# ADC_IN.net
KiCad netlist of a schematic drawn in Altium Designer
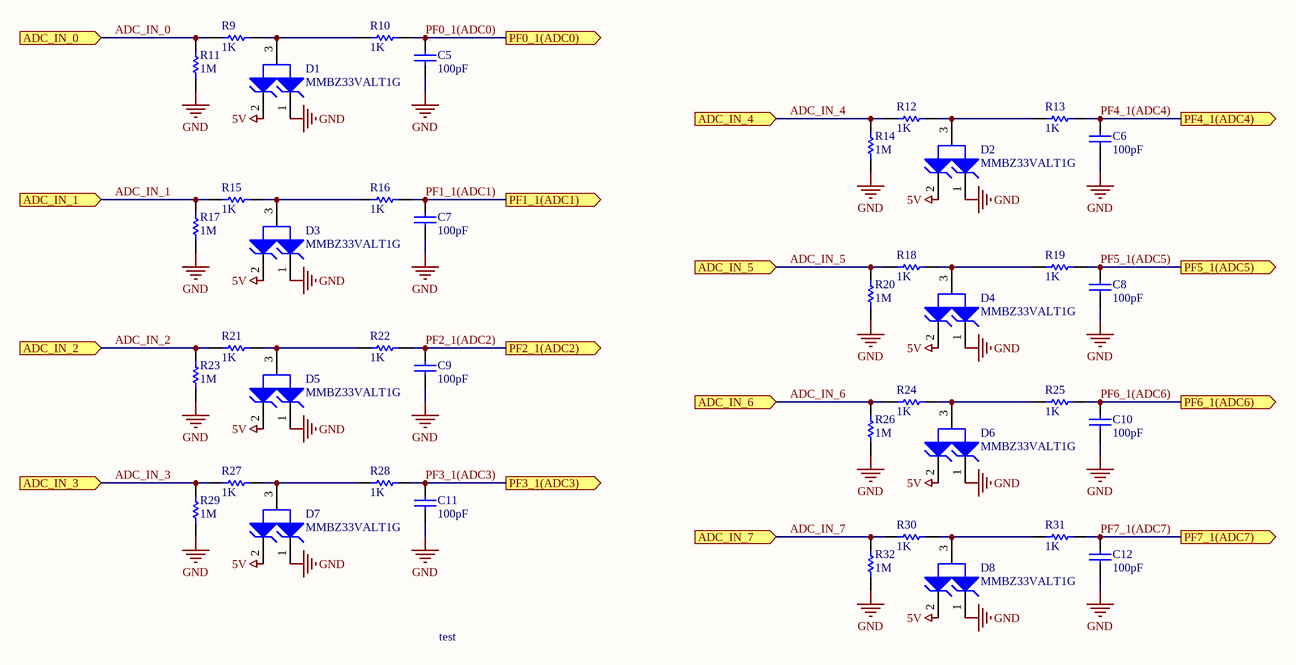
[diagram p0: ADC_IN.SchDoc]

(export (version "E")
  (design (tool "Eeschema 10.0.6"))
  (components
    (comp (ref "C5")
      (value "100pF")
      (footprint "CAPC2013X140X50NL20T25")
      (fields
        (field (name "MANUFACTURER") "AVX Interconnect / Elco")
        (field (name "PART NUMBER") "08051A102JAT2A")
      )
      (libsource (lib "project") (part "CAP"))
    )
    (comp (ref "C6")
      (value "100pF")
      (footprint "CAPC2013X140X50NL20T25")
      (fields
        (field (name "MANUFACTURER") "AVX Interconnect / Elco")
        (field (name "PART NUMBER") "08051A102JAT2A")
      )
      (libsource (lib "project") (part "CAP"))
    )
    (comp (ref "C7")
      (value "100pF")
      (footprint "CAPC2013X140X50NL20T25")
      (fields
        (field (name "MANUFACTURER") "AVX Interconnect / Elco")
        (field (name "PART NUMBER") "08051A102JAT2A")
      )
      (libsource (lib "project") (part "CAP"))
    )
    (comp (ref "C8")
      (value "100pF")
      (footprint "CAPC2013X140X50NL20T25")
      (fields
        (field (name "MANUFACTURER") "AVX Interconnect / Elco")
        (field (name "PART NUMBER") "08051A102JAT2A")
      )
      (libsource (lib "project") (part "CAP"))
    )
    (comp (ref "C9")
      (value "100pF")
      (footprint "CAPC2013X140X50NL20T25")
      (fields
        (field (name "MANUFACTURER") "AVX Interconnect / Elco")
        (field (name "PART NUMBER") "08051A102JAT2A")
      )
      (libsource (lib "project") (part "CAP"))
    )
    (comp (ref "C10")
      (value "100pF")
      (footprint "CAPC2013X140X50NL20T25")
      (fields
        (field (name "MANUFACTURER") "AVX Interconnect / Elco")
        (field (name "PART NUMBER") "08051A102JAT2A")
      )
      (libsource (lib "project") (part "CAP"))
    )
    (comp (ref "C11")
      (value "100pF")
      (footprint "CAPC2013X140X50NL20T25")
      (fields
        (field (name "MANUFACTURER") "AVX Interconnect / Elco")
        (field (name "PART NUMBER") "08051A102JAT2A")
      )
      (libsource (lib "project") (part "CAP"))
    )
    (comp (ref "C12")
      (value "100pF")
      (footprint "CAPC2013X140X50NL20T25")
      (fields
        (field (name "MANUFACTURER") "AVX Interconnect / Elco")
        (field (name "PART NUMBER") "08051A102JAT2A")
      )
      (libsource (lib "project") (part "CAP"))
    )
    (comp (ref "D1")
      (value "MMBZ33VALT1G")
      (footprint "ONSC-SOT-23-3-318-08_V")
      (fields (field (name "MANUFACTURER") "On Semiconductor"))
      (libsource (lib "project") (part "ONSC-K1K2A3-3"))
    )
    (comp (ref "D2")
      (value "MMBZ33VALT1G")
      (footprint "ONSC-SOT-23-3-318-08_V")
      (fields (field (name "MANUFACTURER") "On Semiconductor"))
      (libsource (lib "project") (part "ONSC-K1K2A3-3"))
    )
    (comp (ref "D3")
      (value "MMBZ33VALT1G")
      (footprint "ONSC-SOT-23-3-318-08_V")
      (fields (field (name "MANUFACTURER") "On Semiconductor"))
      (libsource (lib "project") (part "ONSC-K1K2A3-3"))
    )
    (comp (ref "D4")
      (value "MMBZ33VALT1G")
      (footprint "ONSC-SOT-23-3-318-08_V")
      (fields (field (name "MANUFACTURER") "On Semiconductor"))
      (libsource (lib "project") (part "ONSC-K1K2A3-3"))
    )
    (comp (ref "D5")
      (value "MMBZ33VALT1G")
      (footprint "ONSC-SOT-23-3-318-08_V")
      (fields (field (name "MANUFACTURER") "On Semiconductor"))
      (libsource (lib "project") (part "ONSC-K1K2A3-3"))
    )
    (comp (ref "D6")
      (value "MMBZ33VALT1G")
      (footprint "ONSC-SOT-23-3-318-08_V")
      (fields (field (name "MANUFACTURER") "On Semiconductor"))
      (libsource (lib "project") (part "ONSC-K1K2A3-3"))
    )
    (comp (ref "D7")
      (value "MMBZ33VALT1G")
      (footprint "ONSC-SOT-23-3-318-08_V")
      (fields (field (name "MANUFACTURER") "On Semiconductor"))
      (libsource (lib "project") (part "ONSC-K1K2A3-3"))
    )
    (comp (ref "D8")
      (value "MMBZ33VALT1G")
      (footprint "ONSC-SOT-23-3-318-08_V")
      (fields (field (name "MANUFACTURER") "On Semiconductor"))
      (libsource (lib "project") (part "ONSC-K1K2A3-3"))
    )
    (comp (ref "R9")
      (value "1K")
      (footprint "RESC2113X50X35ML15T15")
      (description "Chip Resistor, 4.7 KOhm, +/- 1%, 0.125 W, -55 to 155 degC, 0805 (2012 Metric), RoHS, Tape and Reel")
      (fields (field (name "TOLERANCE") "1%") (field (name "MANUFACTURER") "Vishay Semiconductor"))
      (libsource (lib "project") (part "RES-2"))
    )
    (comp (ref "R10")
      (value "1K")
      (footprint "RESC2113X50X35ML15T15")
      (description "Chip Resistor, 4.7 KOhm, +/- 1%, 0.125 W, -55 to 155 degC, 0805 (2012 Metric), RoHS, Tape and Reel")
      (fields (field (name "TOLERANCE") "1%") (field (name "MANUFACTURER") "Vishay Semiconductor"))
      (libsource (lib "project") (part "RES-2"))
    )
    (comp (ref "R11")
      (value "1M")
      (footprint "RESC2113X50X35ML15T15")
      (description "Chip Resistor, 4.7 KOhm, +/- 1%, 0.125 W, -55 to 155 degC, 0805 (2012 Metric), RoHS, Tape and Reel")
      (fields (field (name "TOLERANCE") "1%") (field (name "MANUFACTURER") "Vishay Semiconductor"))
      (libsource (lib "project") (part "RES-2"))
    )
    (comp (ref "R12")
      (value "1K")
      (footprint "RESC2113X50X35ML15T15")
      (description "Chip Resistor, 4.7 KOhm, +/- 1%, 0.125 W, -55 to 155 degC, 0805 (2012 Metric), RoHS, Tape and Reel")
      (fields (field (name "TOLERANCE") "1%") (field (name "MANUFACTURER") "Vishay Semiconductor"))
      (libsource (lib "project") (part "RES-2"))
    )
    (comp (ref "R13")
      (value "1K")
      (footprint "RESC2113X50X35ML15T15")
      (description "Chip Resistor, 4.7 KOhm, +/- 1%, 0.125 W, -55 to 155 degC, 0805 (2012 Metric), RoHS, Tape and Reel")
      (fields (field (name "TOLERANCE") "1%") (field (name "MANUFACTURER") "Vishay Semiconductor"))
      (libsource (lib "project") (part "RES-2"))
    )
    (comp (ref "R14")
      (value "1M")
      (footprint "RESC2113X50X35ML15T15")
      (description "Chip Resistor, 4.7 KOhm, +/- 1%, 0.125 W, -55 to 155 degC, 0805 (2012 Metric), RoHS, Tape and Reel")
      (fields (field (name "TOLERANCE") "1%") (field (name "MANUFACTURER") "Vishay Semiconductor"))
      (libsource (lib "project") (part "RES-2"))
    )
    (comp (ref "R15")
      (value "1K")
      (footprint "RESC2113X50X35ML15T15")
      (description "Chip Resistor, 4.7 KOhm, +/- 1%, 0.125 W, -55 to 155 degC, 0805 (2012 Metric), RoHS, Tape and Reel")
      (fields (field (name "TOLERANCE") "1%") (field (name "MANUFACTURER") "Vishay Semiconductor"))
      (libsource (lib "project") (part "RES-2"))
    )
    (comp (ref "R16")
      (value "1K")
      (footprint "RESC2113X50X35ML15T15")
      (description "Chip Resistor, 4.7 KOhm, +/- 1%, 0.125 W, -55 to 155 degC, 0805 (2012 Metric), RoHS, Tape and Reel")
      (fields (field (name "TOLERANCE") "1%") (field (name "MANUFACTURER") "Vishay Semiconductor"))
      (libsource (lib "project") (part "RES-2"))
    )
    (comp (ref "R17")
      (value "1M")
      (footprint "RESC2113X50X35ML15T15")
      (description "Chip Resistor, 4.7 KOhm, +/- 1%, 0.125 W, -55 to 155 degC, 0805 (2012 Metric), RoHS, Tape and Reel")
      (fields (field (name "TOLERANCE") "1%") (field (name "MANUFACTURER") "Vishay Semiconductor"))
      (libsource (lib "project") (part "RES-2"))
    )
    (comp (ref "R18")
      (value "1K")
      (footprint "RESC2113X50X35ML15T15")
      (description "Chip Resistor, 4.7 KOhm, +/- 1%, 0.125 W, -55 to 155 degC, 0805 (2012 Metric), RoHS, Tape and Reel")
      (fields (field (name "TOLERANCE") "1%") (field (name "MANUFACTURER") "Vishay Semiconductor"))
      (libsource (lib "project") (part "RES-2"))
    )
    (comp (ref "R19")
      (value "1K")
      (footprint "RESC2113X50X35ML15T15")
      (description "Chip Resistor, 4.7 KOhm, +/- 1%, 0.125 W, -55 to 155 degC, 0805 (2012 Metric), RoHS, Tape and Reel")
      (fields (field (name "TOLERANCE") "1%") (field (name "MANUFACTURER") "Vishay Semiconductor"))
      (libsource (lib "project") (part "RES-2"))
    )
    (comp (ref "R20")
      (value "1M")
      (footprint "RESC2113X50X35ML15T15")
      (description "Chip Resistor, 4.7 KOhm, +/- 1%, 0.125 W, -55 to 155 degC, 0805 (2012 Metric), RoHS, Tape and Reel")
      (fields (field (name "TOLERANCE") "1%") (field (name "MANUFACTURER") "Vishay Semiconductor"))
      (libsource (lib "project") (part "RES-2"))
    )
    (comp (ref "R21")
      (value "1K")
      (footprint "RESC2113X50X35ML15T15")
      (description "Chip Resistor, 4.7 KOhm, +/- 1%, 0.125 W, -55 to 155 degC, 0805 (2012 Metric), RoHS, Tape and Reel")
      (fields (field (name "TOLERANCE") "1%") (field (name "MANUFACTURER") "Vishay Semiconductor"))
      (libsource (lib "project") (part "RES-2"))
    )
    (comp (ref "R22")
      (value "1K")
      (footprint "RESC2113X50X35ML15T15")
      (description "Chip Resistor, 4.7 KOhm, +/- 1%, 0.125 W, -55 to 155 degC, 0805 (2012 Metric), RoHS, Tape and Reel")
      (fields (field (name "TOLERANCE") "1%") (field (name "MANUFACTURER") "Vishay Semiconductor"))
      (libsource (lib "project") (part "RES-2"))
    )
    (comp (ref "R23")
      (value "1M")
      (footprint "RESC2113X50X35ML15T15")
      (description "Chip Resistor, 4.7 KOhm, +/- 1%, 0.125 W, -55 to 155 degC, 0805 (2012 Metric), RoHS, Tape and Reel")
      (fields (field (name "TOLERANCE") "1%") (field (name "MANUFACTURER") "Vishay Semiconductor"))
      (libsource (lib "project") (part "RES-2"))
    )
    (comp (ref "R24")
      (value "1K")
      (footprint "RESC2113X50X35ML15T15")
      (description "Chip Resistor, 4.7 KOhm, +/- 1%, 0.125 W, -55 to 155 degC, 0805 (2012 Metric), RoHS, Tape and Reel")
      (fields (field (name "TOLERANCE") "1%") (field (name "MANUFACTURER") "Vishay Semiconductor"))
      (libsource (lib "project") (part "RES-2"))
    )
    (comp (ref "R25")
      (value "1K")
      (footprint "RESC2113X50X35ML15T15")
      (description "Chip Resistor, 4.7 KOhm, +/- 1%, 0.125 W, -55 to 155 degC, 0805 (2012 Metric), RoHS, Tape and Reel")
      (fields (field (name "TOLERANCE") "1%") (field (name "MANUFACTURER") "Vishay Semiconductor"))
      (libsource (lib "project") (part "RES-2"))
    )
    (comp (ref "R26")
      (value "1M")
      (footprint "RESC2113X50X35ML15T15")
      (description "Chip Resistor, 4.7 KOhm, +/- 1%, 0.125 W, -55 to 155 degC, 0805 (2012 Metric), RoHS, Tape and Reel")
      (fields (field (name "TOLERANCE") "1%") (field (name "MANUFACTURER") "Vishay Semiconductor"))
      (libsource (lib "project") (part "RES-2"))
    )
    (comp (ref "R27")
      (value "1K")
      (footprint "RESC2113X50X35ML15T15")
      (description "Chip Resistor, 4.7 KOhm, +/- 1%, 0.125 W, -55 to 155 degC, 0805 (2012 Metric), RoHS, Tape and Reel")
      (fields (field (name "TOLERANCE") "1%") (field (name "MANUFACTURER") "Vishay Semiconductor"))
      (libsource (lib "project") (part "RES-2"))
    )
    (comp (ref "R28")
      (value "1K")
      (footprint "RESC2113X50X35ML15T15")
      (description "Chip Resistor, 4.7 KOhm, +/- 1%, 0.125 W, -55 to 155 degC, 0805 (2012 Metric), RoHS, Tape and Reel")
      (fields (field (name "TOLERANCE") "1%") (field (name "MANUFACTURER") "Vishay Semiconductor"))
      (libsource (lib "project") (part "RES-2"))
    )
    (comp (ref "R29")
      (value "1M")
      (footprint "RESC2113X50X35ML15T15")
      (description "Chip Resistor, 4.7 KOhm, +/- 1%, 0.125 W, -55 to 155 degC, 0805 (2012 Metric), RoHS, Tape and Reel")
      (fields (field (name "TOLERANCE") "1%") (field (name "MANUFACTURER") "Vishay Semiconductor"))
      (libsource (lib "project") (part "RES-2"))
    )
    (comp (ref "R30")
      (value "1K")
      (footprint "RESC2113X50X35ML15T15")
      (description "Chip Resistor, 4.7 KOhm, +/- 1%, 0.125 W, -55 to 155 degC, 0805 (2012 Metric), RoHS, Tape and Reel")
      (fields (field (name "TOLERANCE") "1%") (field (name "MANUFACTURER") "Vishay Semiconductor"))
      (libsource (lib "project") (part "RES-2"))
    )
    (comp (ref "R31")
      (value "1K")
      (footprint "RESC2113X50X35ML15T15")
      (description "Chip Resistor, 4.7 KOhm, +/- 1%, 0.125 W, -55 to 155 degC, 0805 (2012 Metric), RoHS, Tape and Reel")
      (fields (field (name "TOLERANCE") "1%") (field (name "MANUFACTURER") "Vishay Semiconductor"))
      (libsource (lib "project") (part "RES-2"))
    )
    (comp (ref "R32")
      (value "1M")
      (footprint "RESC2113X50X35ML15T15")
      (description "Chip Resistor, 4.7 KOhm, +/- 1%, 0.125 W, -55 to 155 degC, 0805 (2012 Metric), RoHS, Tape and Reel")
      (fields (field (name "TOLERANCE") "1%") (field (name "MANUFACTURER") "Vishay Semiconductor"))
      (libsource (lib "project") (part "RES-2"))
    )
  )
  (nets
    (net (code "1") (name "/ADC_IN_0") (class "Default")
      (node (ref "R11") (pin "1") (pinfunction "1_1") (pintype "passive"))
      (node (ref "R9") (pin "2") (pinfunction "2_2") (pintype "passive"))
    )
    (net (code "2") (name "/ADC_IN_1") (class "Default")
      (node (ref "R15") (pin "2") (pinfunction "2_2") (pintype "passive"))
      (node (ref "R17") (pin "1") (pinfunction "1_1") (pintype "passive"))
    )
    (net (code "3") (name "/ADC_IN_2") (class "Default")
      (node (ref "R21") (pin "2") (pinfunction "2_2") (pintype "passive"))
      (node (ref "R23") (pin "1") (pinfunction "1_1") (pintype "passive"))
    )
    (net (code "4") (name "/ADC_IN_3") (class "Default")
      (node (ref "R27") (pin "2") (pinfunction "2_2") (pintype "passive"))
      (node (ref "R29") (pin "1") (pinfunction "1_1") (pintype "passive"))
    )
    (net (code "5") (name "/ADC_IN_4") (class "Default")
      (node (ref "R12") (pin "2") (pinfunction "2_2") (pintype "passive"))
      (node (ref "R14") (pin "1") (pinfunction "1_1") (pintype "passive"))
    )
    (net (code "6") (name "/ADC_IN_5") (class "Default")
      (node (ref "R18") (pin "2") (pinfunction "2_2") (pintype "passive"))
      (node (ref "R20") (pin "1") (pinfunction "1_1") (pintype "passive"))
    )
    (net (code "7") (name "/ADC_IN_6") (class "Default")
      (node (ref "R24") (pin "2") (pinfunction "2_2") (pintype "passive"))
      (node (ref "R26") (pin "1") (pinfunction "1_1") (pintype "passive"))
    )
    (net (code "8") (name "/ADC_IN_7") (class "Default")
      (node (ref "R30") (pin "2") (pinfunction "2_2") (pintype "passive"))
      (node (ref "R32") (pin "1") (pinfunction "1_1") (pintype "passive"))
    )
    (net (code "9") (name "/PF0_1(ADC0)") (class "Default")
      (node (ref "C5") (pin "1") (pinfunction "1_1") (pintype "passive"))
      (node (ref "R10") (pin "1") (pinfunction "1_1") (pintype "passive"))
    )
    (net (code "10") (name "/PF1_1(ADC1)") (class "Default")
      (node (ref "C7") (pin "1") (pinfunction "1_1") (pintype "passive"))
      (node (ref "R16") (pin "1") (pinfunction "1_1") (pintype "passive"))
    )
    (net (code "11") (name "/PF2_1(ADC2)") (class "Default")
      (node (ref "C9") (pin "1") (pinfunction "1_1") (pintype "passive"))
      (node (ref "R22") (pin "1") (pinfunction "1_1") (pintype "passive"))
    )
    (net (code "12") (name "/PF3_1(ADC3)") (class "Default")
      (node (ref "C11") (pin "1") (pinfunction "1_1") (pintype "passive"))
      (node (ref "R28") (pin "1") (pinfunction "1_1") (pintype "passive"))
    )
    (net (code "13") (name "/PF4_1(ADC4)") (class "Default")
      (node (ref "C6") (pin "1") (pinfunction "1_1") (pintype "passive"))
      (node (ref "R13") (pin "1") (pinfunction "1_1") (pintype "passive"))
    )
    (net (code "14") (name "/PF5_1(ADC5)") (class "Default")
      (node (ref "C8") (pin "1") (pinfunction "1_1") (pintype "passive"))
      (node (ref "R19") (pin "1") (pinfunction "1_1") (pintype "passive"))
    )
    (net (code "15") (name "/PF6_1(ADC6)") (class "Default")
      (node (ref "C10") (pin "1") (pinfunction "1_1") (pintype "passive"))
      (node (ref "R25") (pin "1") (pinfunction "1_1") (pintype "passive"))
    )
    (net (code "16") (name "/PF7_1(ADC7)") (class "Default")
      (node (ref "C12") (pin "1") (pinfunction "1_1") (pintype "passive"))
      (node (ref "R31") (pin "1") (pinfunction "1_1") (pintype "passive"))
    )
    (net (code "17") (name "5V") (class "Default")
      (node (ref "D1") (pin "2") (pinfunction "K2_2") (pintype "passive"))
      (node (ref "D2") (pin "2") (pinfunction "K2_2") (pintype "passive"))
      (node (ref "D3") (pin "2") (pinfunction "K2_2") (pintype "passive"))
      (node (ref "D4") (pin "2") (pinfunction "K2_2") (pintype "passive"))
      (node (ref "D5") (pin "2") (pinfunction "K2_2") (pintype "passive"))
      (node (ref "D6") (pin "2") (pinfunction "K2_2") (pintype "passive"))
      (node (ref "D7") (pin "2") (pinfunction "K2_2") (pintype "passive"))
      (node (ref "D8") (pin "2") (pinfunction "K2_2") (pintype "passive"))
    )
    (net (code "18") (name "GND") (class "Default")
      (node (ref "C10") (pin "2") (pinfunction "2_2") (pintype "passive"))
      (node (ref "C11") (pin "2") (pinfunction "2_2") (pintype "passive"))
      (node (ref "C12") (pin "2") (pinfunction "2_2") (pintype "passive"))
      (node (ref "C5") (pin "2") (pinfunction "2_2") (pintype "passive"))
      (node (ref "C6") (pin "2") (pinfunction "2_2") (pintype "passive"))
      (node (ref "C7") (pin "2") (pinfunction "2_2") (pintype "passive"))
      (node (ref "C8") (pin "2") (pinfunction "2_2") (pintype "passive"))
      (node (ref "C9") (pin "2") (pinfunction "2_2") (pintype "passive"))
      (node (ref "D1") (pin "1") (pinfunction "K1_1") (pintype "passive"))
      (node (ref "D2") (pin "1") (pinfunction "K1_1") (pintype "passive"))
      (node (ref "D3") (pin "1") (pinfunction "K1_1") (pintype "passive"))
      (node (ref "D4") (pin "1") (pinfunction "K1_1") (pintype "passive"))
      (node (ref "D5") (pin "1") (pinfunction "K1_1") (pintype "passive"))
      (node (ref "D6") (pin "1") (pinfunction "K1_1") (pintype "passive"))
      (node (ref "D7") (pin "1") (pinfunction "K1_1") (pintype "passive"))
      (node (ref "D8") (pin "1") (pinfunction "K1_1") (pintype "passive"))
      (node (ref "R11") (pin "2") (pinfunction "2_2") (pintype "passive"))
      (node (ref "R14") (pin "2") (pinfunction "2_2") (pintype "passive"))
      (node (ref "R17") (pin "2") (pinfunction "2_2") (pintype "passive"))
      (node (ref "R20") (pin "2") (pinfunction "2_2") (pintype "passive"))
      (node (ref "R23") (pin "2") (pinfunction "2_2") (pintype "passive"))
      (node (ref "R26") (pin "2") (pinfunction "2_2") (pintype "passive"))
      (node (ref "R29") (pin "2") (pinfunction "2_2") (pintype "passive"))
      (node (ref "R32") (pin "2") (pinfunction "2_2") (pintype "passive"))
    )
    (net (code "19") (name "Net-(D1-A)") (class "Default")
      (node (ref "D1") (pin "3") (pinfunction "A_3") (pintype "passive"))
      (node (ref "R10") (pin "2") (pinfunction "2_2") (pintype "passive"))
      (node (ref "R9") (pin "1") (pinfunction "1_1") (pintype "passive"))
    )
    (net (code "20") (name "Net-(D2-A)") (class "Default")
      (node (ref "D2") (pin "3") (pinfunction "A_3") (pintype "passive"))
      (node (ref "R12") (pin "1") (pinfunction "1_1") (pintype "passive"))
      (node (ref "R13") (pin "2") (pinfunction "2_2") (pintype "passive"))
    )
    (net (code "21") (name "Net-(D3-A)") (class "Default")
      (node (ref "D3") (pin "3") (pinfunction "A_3") (pintype "passive"))
      (node (ref "R15") (pin "1") (pinfunction "1_1") (pintype "passive"))
      (node (ref "R16") (pin "2") (pinfunction "2_2") (pintype "passive"))
    )
    (net (code "22") (name "Net-(D4-A)") (class "Default")
      (node (ref "D4") (pin "3") (pinfunction "A_3") (pintype "passive"))
      (node (ref "R18") (pin "1") (pinfunction "1_1") (pintype "passive"))
      (node (ref "R19") (pin "2") (pinfunction "2_2") (pintype "passive"))
    )
    (net (code "23") (name "Net-(D5-A)") (class "Default")
      (node (ref "D5") (pin "3") (pinfunction "A_3") (pintype "passive"))
      (node (ref "R21") (pin "1") (pinfunction "1_1") (pintype "passive"))
      (node (ref "R22") (pin "2") (pinfunction "2_2") (pintype "passive"))
    )
    (net (code "24") (name "Net-(D6-A)") (class "Default")
      (node (ref "D6") (pin "3") (pinfunction "A_3") (pintype "passive"))
      (node (ref "R24") (pin "1") (pinfunction "1_1") (pintype "passive"))
      (node (ref "R25") (pin "2") (pinfunction "2_2") (pintype "passive"))
    )
    (net (code "25") (name "Net-(D7-A)") (class "Default")
      (node (ref "D7") (pin "3") (pinfunction "A_3") (pintype "passive"))
      (node (ref "R27") (pin "1") (pinfunction "1_1") (pintype "passive"))
      (node (ref "R28") (pin "2") (pinfunction "2_2") (pintype "passive"))
    )
    (net (code "26") (name "Net-(D8-A)") (class "Default")
      (node (ref "D8") (pin "3") (pinfunction "A_3") (pintype "passive"))
      (node (ref "R30") (pin "1") (pinfunction "1_1") (pintype "passive"))
      (node (ref "R31") (pin "2") (pinfunction "2_2") (pintype "passive"))
    )
  )
)
